# Grove_-_I2C_High_Accuracy_Temp_Humi_Sens.net
KiCad netlist of a schematic drawn in EAGLE
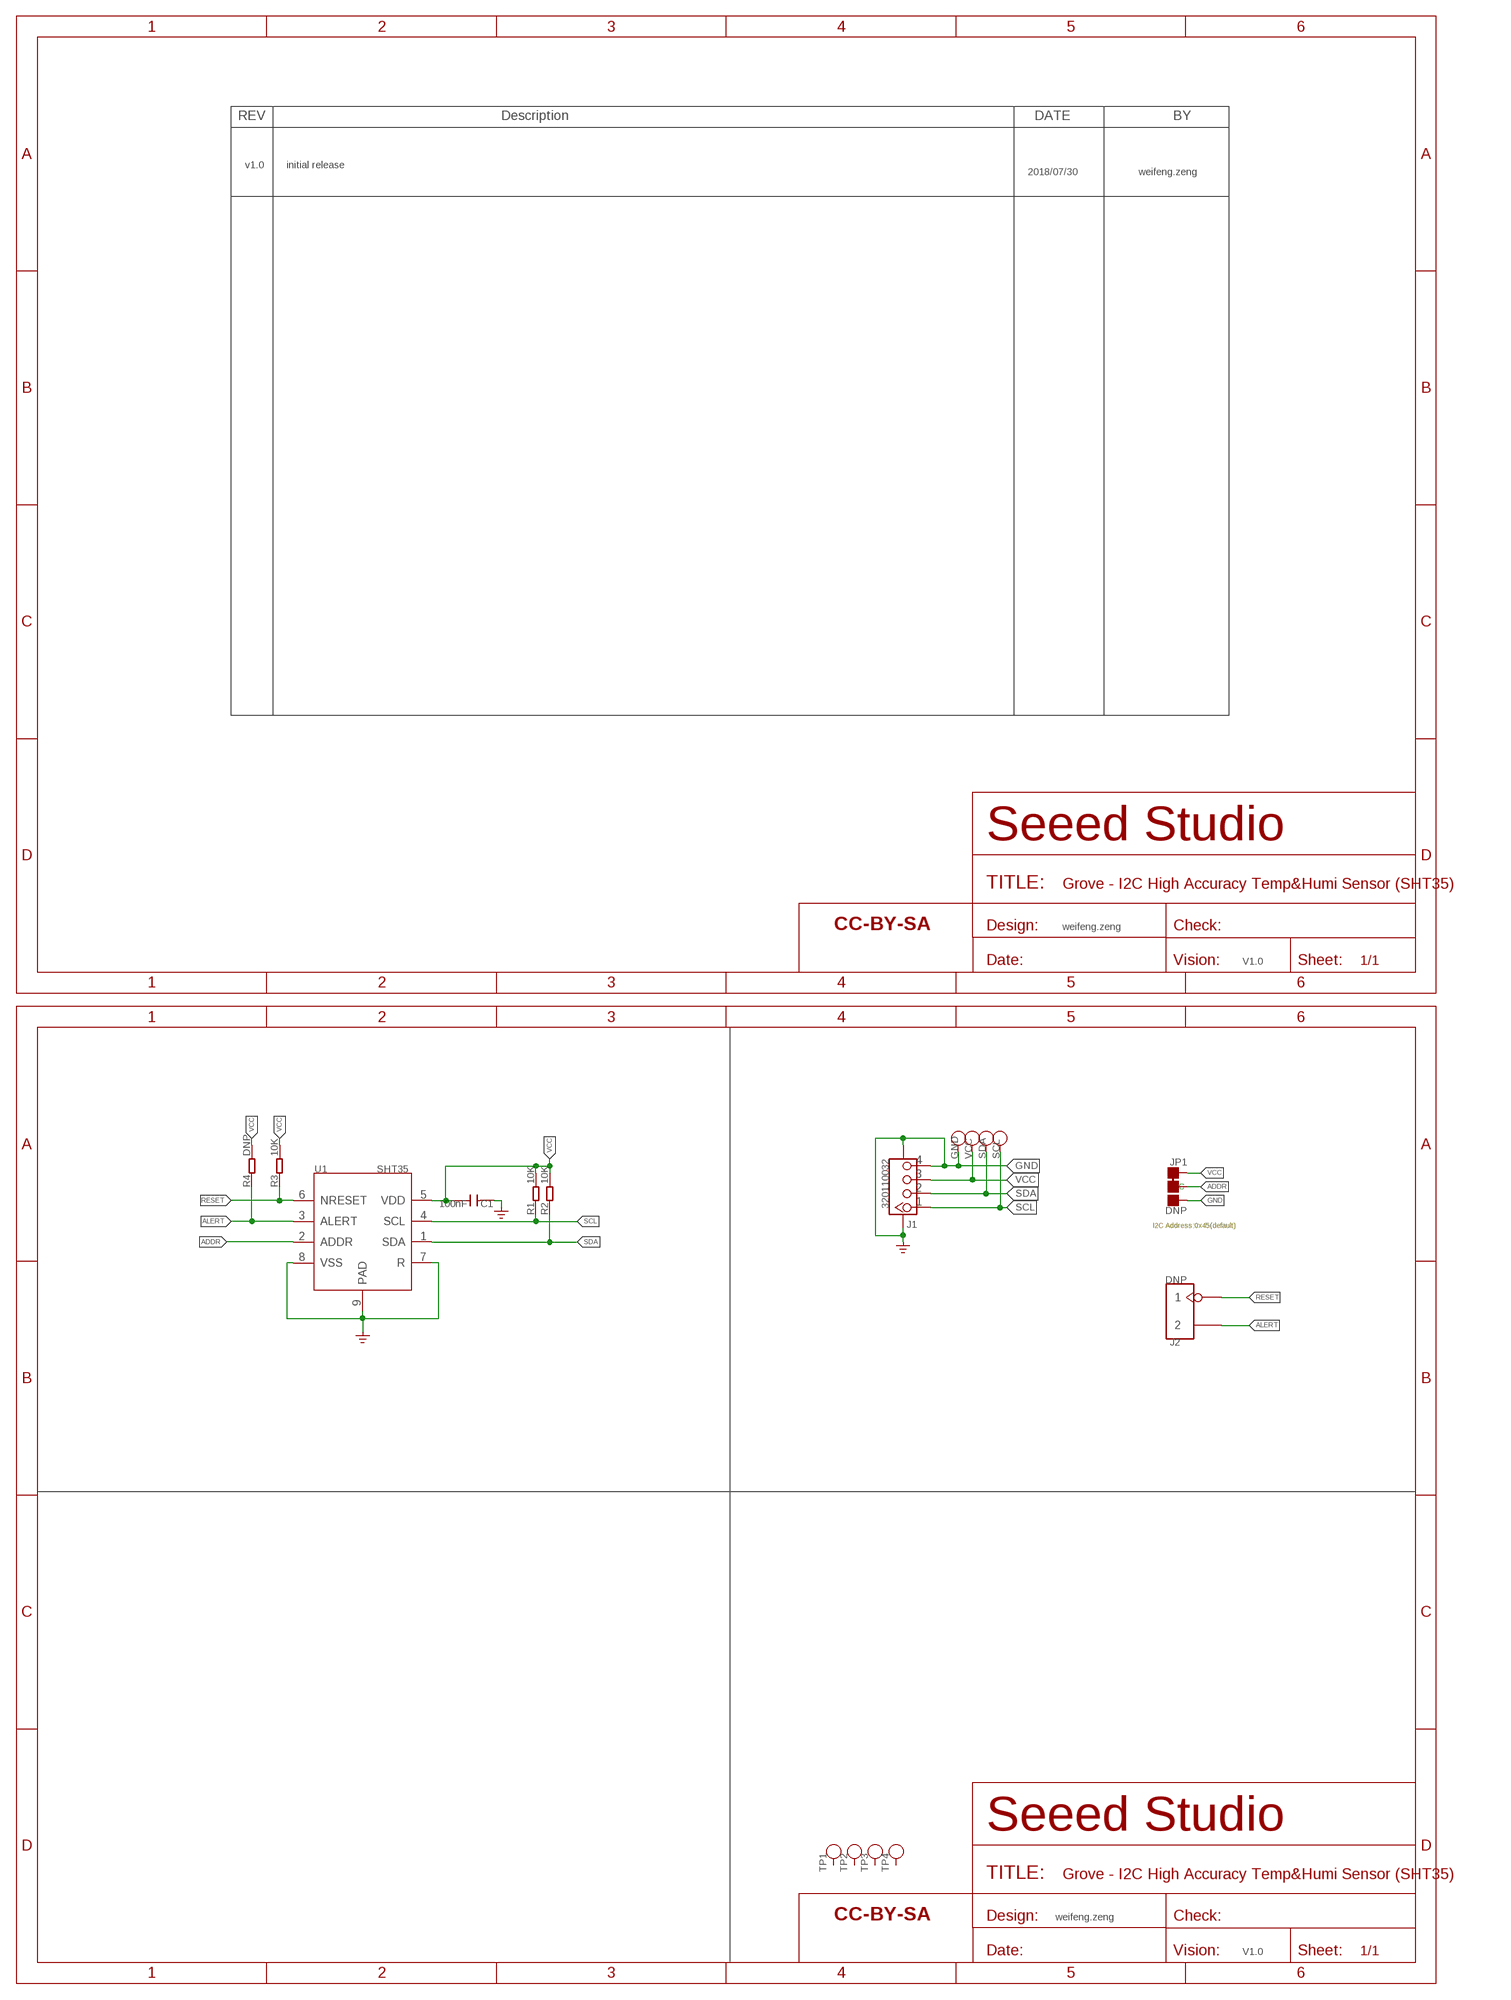
[diagram p0: schematic, sheet 1]

(export (version "E")
  (design (tool "Eeschema 10.0.6"))
  (components
    (comp (ref "C1")
      (value "100nF")
      (footprint "eagle-import:C0603")
      (libsource (lib "eagle-import") (part "CAP-0603"))
    )
    (comp (ref "FR1")
      (value "SEEEDSTUDIO-OPEN-SCH-FRAME")
      (footprint "eagle-import:SEEEDSTUDIO-PCB-FRAME")
      (libsource (lib "eagle-import") (part "SEEEDSTUDIO-OPEN-SCH-FRAME"))
    )
    (comp (ref "FR2")
      (value "SEEEDSTUDIO-OPEN-SCH-FRAME")
      (footprint "eagle-import:SEEEDSTUDIO-PCB-FRAME")
      (libsource (lib "eagle-import") (part "SEEEDSTUDIO-OPEN-SCH-FRAME"))
    )
    (comp (ref "GND")
      (value "TEST-POINT'4545'")
      (footprint "eagle-import:TP-D45MIL")
      (fields (field (name "PARTNO") "DNP"))
      (libsource (lib "eagle-import") (part "TEST-POINT'4545'"))
    )
    (comp (ref "J1")
      (value "320110032")
      (footprint "eagle-import:HW4-SMD-2.0-90D")
      (libsource (lib "eagle-import") (part "GROVE-CONNECTOR-SMD'90D'"))
    )
    (comp (ref "J2")
      (value "DNP")
      (footprint "eagle-import:H2-2.54")
      (libsource (lib "eagle-import") (part "HEADER-2P-65/35MIL"))
    )
    (comp (ref "JP1")
      (value "DNP")
      (footprint "eagle-import:3P-SMD-SHORT")
      (libsource (lib "eagle-import") (part "JP-3P-SHORT"))
    )
    (comp (ref "R1")
      (value "10K")
      (footprint "eagle-import:R0603")
      (libsource (lib "eagle-import") (part "RES-0603"))
    )
    (comp (ref "R2")
      (value "10K")
      (footprint "eagle-import:R0603")
      (libsource (lib "eagle-import") (part "RES-0603"))
    )
    (comp (ref "R3")
      (value "10K")
      (footprint "eagle-import:R0603")
      (libsource (lib "eagle-import") (part "RES-0603"))
    )
    (comp (ref "R4")
      (value "DNP")
      (footprint "eagle-import:R0603")
      (libsource (lib "eagle-import") (part "RES-0603"))
    )
    (comp (ref "SCL")
      (value "TEST-POINT'4545'")
      (footprint "eagle-import:TP-D45MIL")
      (fields (field (name "PARTNO") "DNP"))
      (libsource (lib "eagle-import") (part "TEST-POINT'4545'"))
    )
    (comp (ref "SDA")
      (value "TEST-POINT'4545'")
      (footprint "eagle-import:TP-D45MIL")
      (fields (field (name "PARTNO") "DNP"))
      (libsource (lib "eagle-import") (part "TEST-POINT'4545'"))
    )
    (comp (ref "TP1")
      (value "TEST-POINT'4545'")
      (footprint "eagle-import:TP-D45MIL")
      (fields (field (name "PARTNO") "DNP"))
      (libsource (lib "eagle-import") (part "TEST-POINT'4545'"))
    )
    (comp (ref "TP2")
      (value "TEST-POINT'4545'")
      (footprint "eagle-import:TP-D45MIL")
      (fields (field (name "PARTNO") "DNP"))
      (libsource (lib "eagle-import") (part "TEST-POINT'4545'"))
    )
    (comp (ref "TP3")
      (value "TEST-POINT'4545'")
      (footprint "eagle-import:TP-D45MIL")
      (fields (field (name "PARTNO") "DNP"))
      (libsource (lib "eagle-import") (part "TEST-POINT'4545'"))
    )
    (comp (ref "TP4")
      (value "TEST-POINT'4545'")
      (footprint "eagle-import:TP-D45MIL")
      (fields (field (name "PARTNO") "DNP"))
      (libsource (lib "eagle-import") (part "TEST-POINT'4545'"))
    )
    (comp (ref "U1")
      (value "SHT35")
      (footprint "eagle-import:DFN8-0.5-2.5X2.5MM")
      (libsource (lib "eagle-import") (part "SENSOR-SHT3X-DIS"))
    )
    (comp (ref "VCC")
      (value "TEST-POINT'4545'")
      (footprint "eagle-import:TP-D45MIL")
      (fields (field (name "PARTNO") "DNP"))
      (libsource (lib "eagle-import") (part "TEST-POINT'4545'"))
    )
  )
  (nets
    (net (code "1") (name "ADDR") (class "Default")
      (node (ref "JP1") (pin "MM") (pinfunction "C_MM") (pintype "bidirectional"))
      (node (ref "U1") (pin "2") (pinfunction "ADDR_2") (pintype "bidirectional"))
    )
    (net (code "2") (name "ALERT") (class "Default")
      (node (ref "J2") (pin "2") (pinfunction "2_2") (pintype "bidirectional"))
      (node (ref "R4") (pin "1") (pinfunction "1_1") (pintype "passive"))
      (node (ref "U1") (pin "3") (pinfunction "ALERT_3") (pintype "bidirectional"))
    )
    (net (code "3") (name "GND") (class "Default")
      (node (ref "C1") (pin "2") (pinfunction "2_2") (pintype "passive"))
      (node (ref "GND") (pin "T") (pinfunction "T_T") (pintype "bidirectional"))
      (node (ref "J1") (pin "4") (pinfunction "4_4") (pintype "bidirectional"))
      (node (ref "J1") (pin "SS1") (pinfunction "SS1_SS1") (pintype "bidirectional"))
      (node (ref "J1") (pin "SS2") (pinfunction "SS2_SS2") (pintype "bidirectional"))
      (node (ref "JP1") (pin "00") (pinfunction "R_00") (pintype "bidirectional"))
      (node (ref "U1") (pin "7") (pinfunction "R_7") (pintype "bidirectional"))
      (node (ref "U1") (pin "8") (pinfunction "VSS_8") (pintype "bidirectional"))
      (node (ref "U1") (pin "9") (pinfunction "PAD_9") (pintype "bidirectional"))
    )
    (net (code "4") (name "RESET") (class "Default")
      (node (ref "J2") (pin "1") (pinfunction "1_1") (pintype "bidirectional"))
      (node (ref "R3") (pin "1") (pinfunction "1_1") (pintype "passive"))
      (node (ref "U1") (pin "6") (pinfunction "NRESET_6") (pintype "bidirectional"))
    )
    (net (code "5") (name "SCL") (class "Default")
      (node (ref "J1") (pin "1") (pinfunction "1_1") (pintype "bidirectional"))
      (node (ref "R1") (pin "1") (pinfunction "1_1") (pintype "passive"))
      (node (ref "SCL") (pin "T") (pinfunction "T_T") (pintype "bidirectional"))
      (node (ref "U1") (pin "4") (pinfunction "SCL_4") (pintype "bidirectional"))
    )
    (net (code "6") (name "SDA") (class "Default")
      (node (ref "J1") (pin "2") (pinfunction "2_2") (pintype "bidirectional"))
      (node (ref "R2") (pin "1") (pinfunction "1_1") (pintype "passive"))
      (node (ref "SDA") (pin "T") (pinfunction "T_T") (pintype "bidirectional"))
      (node (ref "U1") (pin "1") (pinfunction "SDA_1") (pintype "bidirectional"))
    )
    (net (code "7") (name "VCC") (class "Default")
      (node (ref "C1") (pin "1") (pinfunction "1_1") (pintype "passive"))
      (node (ref "J1") (pin "3") (pinfunction "3_3") (pintype "bidirectional"))
      (node (ref "JP1") (pin "11") (pinfunction "L_11") (pintype "bidirectional"))
      (node (ref "R1") (pin "2") (pinfunction "2_2") (pintype "passive"))
      (node (ref "R2") (pin "2") (pinfunction "2_2") (pintype "passive"))
      (node (ref "R3") (pin "2") (pinfunction "2_2") (pintype "passive"))
      (node (ref "R4") (pin "2") (pinfunction "2_2") (pintype "passive"))
      (node (ref "U1") (pin "5") (pinfunction "VDD_5") (pintype "bidirectional"))
      (node (ref "VCC") (pin "T") (pinfunction "T_T") (pintype "bidirectional"))
    )
    (net (code "8") (name "unconnected-(TP1-PadT)") (class "Default")
      (node (ref "TP1") (pin "T") (pinfunction "T_T") (pintype "bidirectional"))
    )
    (net (code "9") (name "unconnected-(TP2-PadT)") (class "Default")
      (node (ref "TP2") (pin "T") (pinfunction "T_T") (pintype "bidirectional"))
    )
    (net (code "10") (name "unconnected-(TP3-PadT)") (class "Default")
      (node (ref "TP3") (pin "T") (pinfunction "T_T") (pintype "bidirectional"))
    )
    (net (code "11") (name "unconnected-(TP4-PadT)") (class "Default")
      (node (ref "TP4") (pin "T") (pinfunction "T_T") (pintype "bidirectional"))
    )
  )
)
